# DorMouse-V1_0.net
KiCad netlist of a schematic drawn in EAGLE
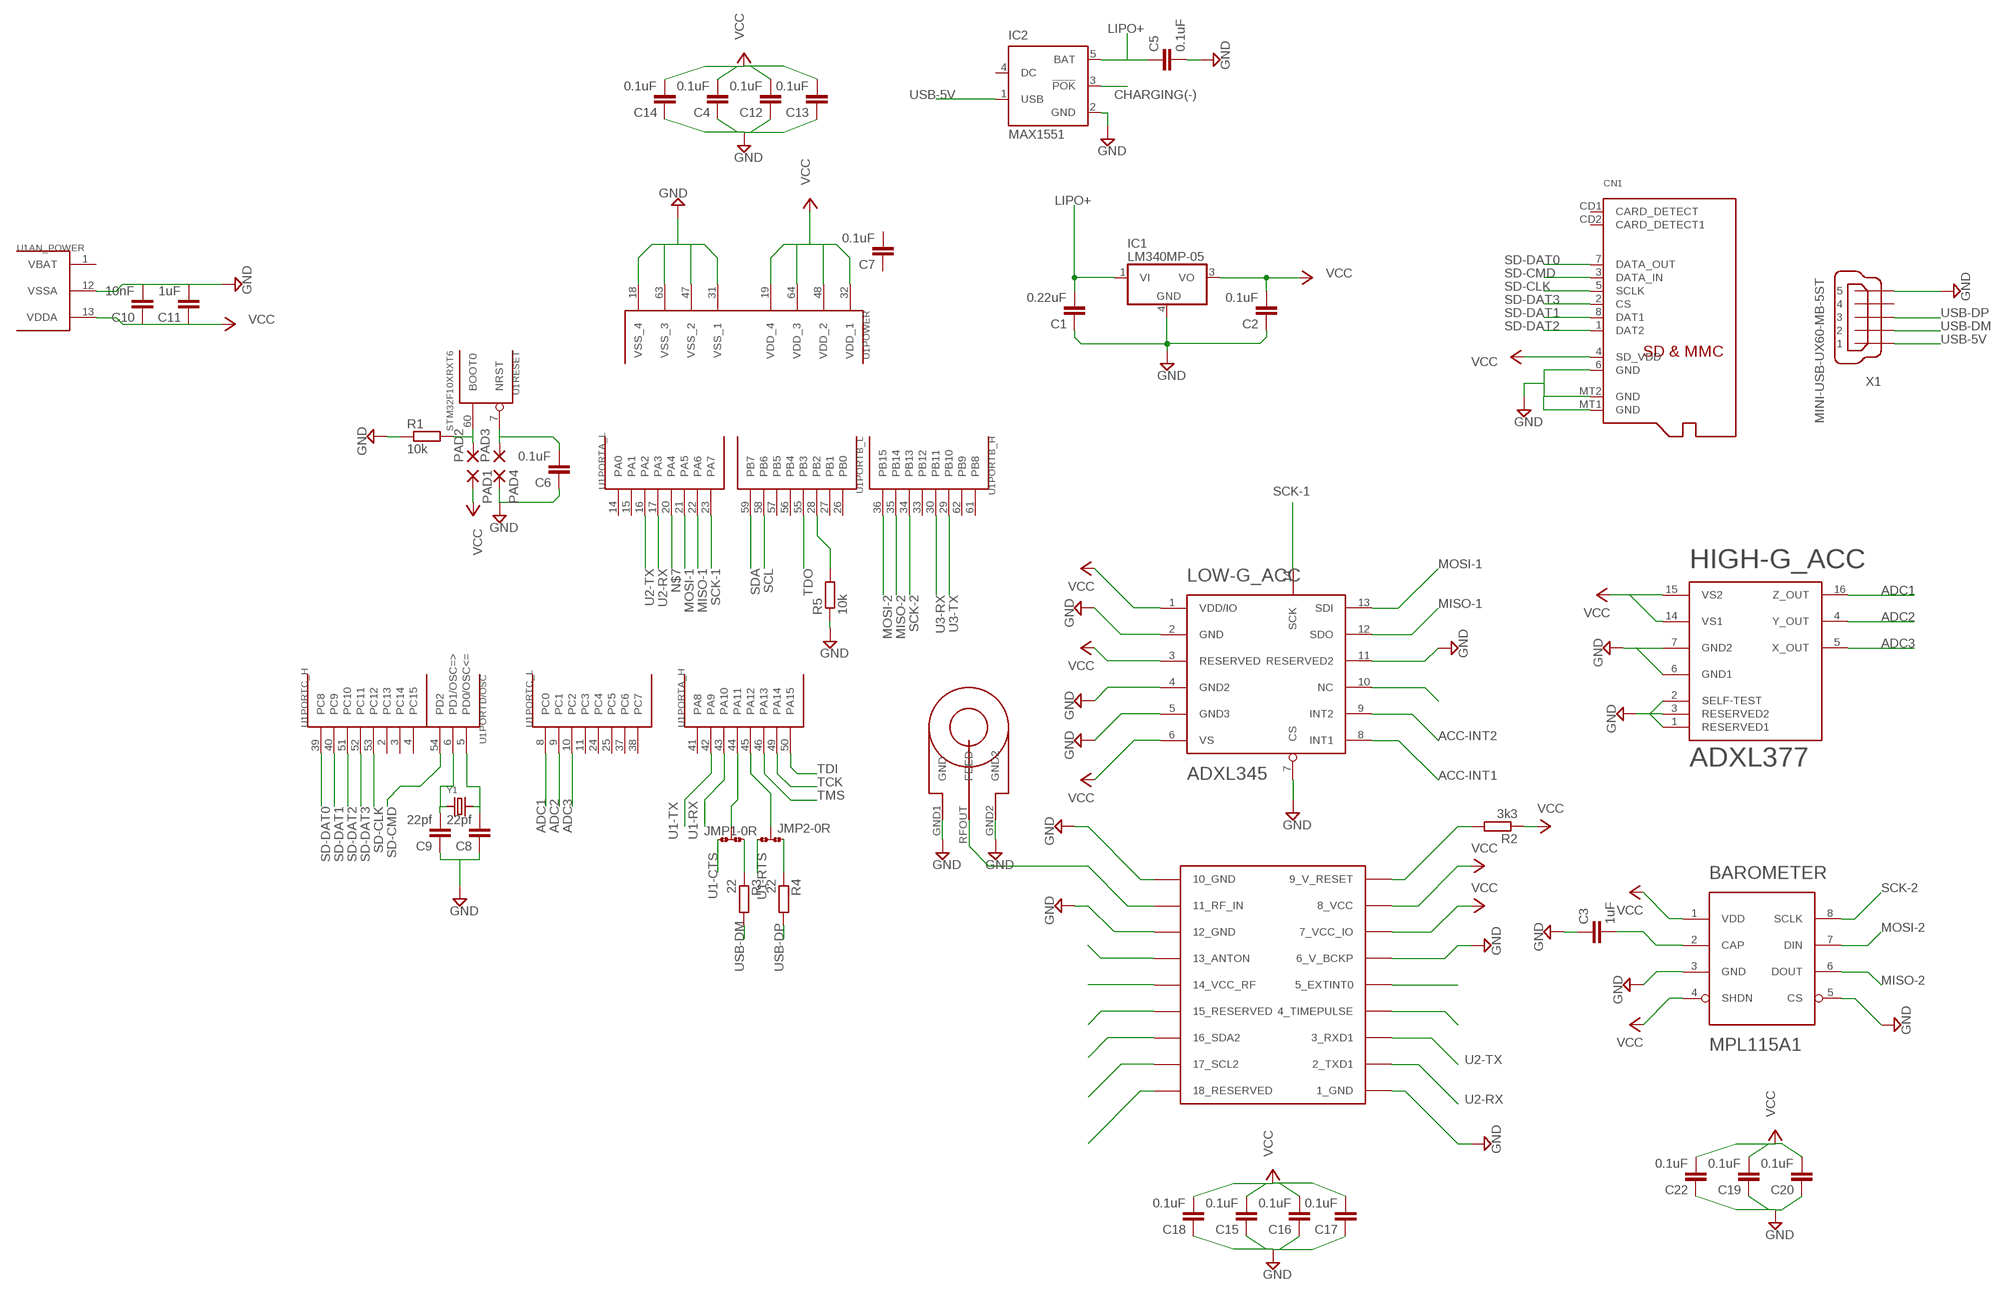
[diagram p0: schematic, sheet 1, part 1 of 2]
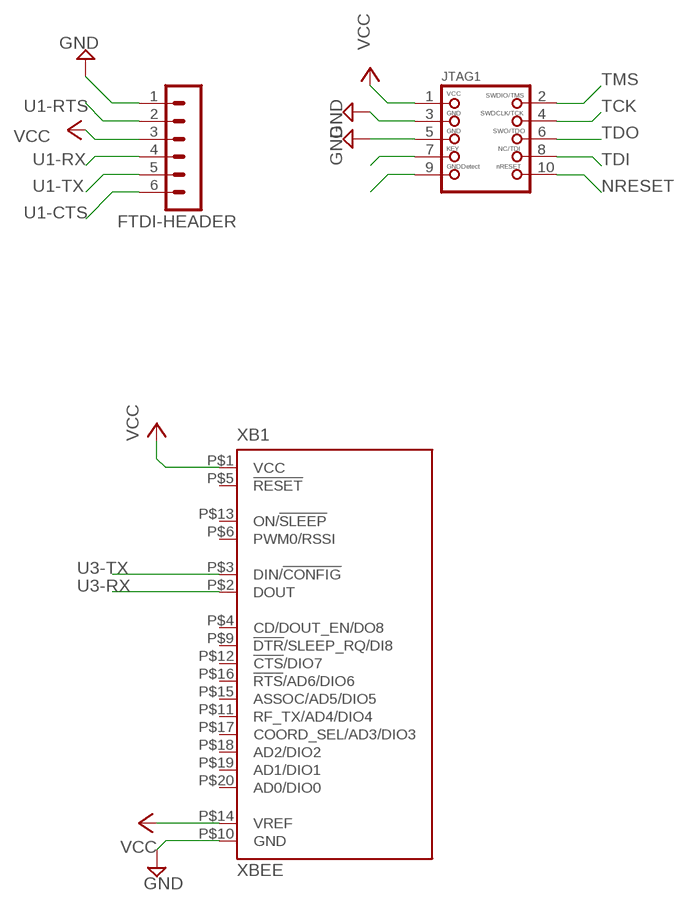
[diagram p1: schematic, sheet 1, part 2 of 2]

(export (version "E")
  (design (tool "Eeschema 10.0.6"))
  (components
    (comp (ref "BAROMETER")
      (value "MPL115A1")
      (footprint "eagle-import:LGA-8")
      (libsource (lib "eagle-import") (part "MPL115A1"))
    )
    (comp (ref "C1")
      (value "0.22uF")
      (footprint "eagle-import:C0402")
      (libsource (lib "eagle-import") (part "C-EUC0402"))
    )
    (comp (ref "C2")
      (value "0.1uF")
      (footprint "eagle-import:C0402")
      (libsource (lib "eagle-import") (part "C-EUC0402"))
    )
    (comp (ref "C3")
      (value "1uF")
      (footprint "eagle-import:C0402")
      (libsource (lib "eagle-import") (part "C-EUC0402"))
    )
    (comp (ref "C4")
      (value "0.1uF")
      (footprint "eagle-import:C0402")
      (libsource (lib "eagle-import") (part "C-EUC0402"))
    )
    (comp (ref "C5")
      (value "0.1uF")
      (footprint "eagle-import:C0402")
      (libsource (lib "eagle-import") (part "C-EUC0402"))
    )
    (comp (ref "C6")
      (value "0.1uF")
      (footprint "eagle-import:C0402")
      (libsource (lib "eagle-import") (part "C-EUC0402"))
    )
    (comp (ref "C7")
      (value "0.1uF")
      (footprint "eagle-import:C0402")
      (libsource (lib "eagle-import") (part "C-EUC0402"))
    )
    (comp (ref "C8")
      (value "22pf")
      (footprint "eagle-import:C0402")
      (libsource (lib "eagle-import") (part "C-EUC0402"))
    )
    (comp (ref "C9")
      (value "22pf")
      (footprint "eagle-import:C0402")
      (libsource (lib "eagle-import") (part "C-EUC0402"))
    )
    (comp (ref "C10")
      (value "10nF")
      (footprint "eagle-import:C0402")
      (libsource (lib "eagle-import") (part "C-EUC0402"))
    )
    (comp (ref "C11")
      (value "1uF")
      (footprint "eagle-import:C0402")
      (libsource (lib "eagle-import") (part "C-EUC0402"))
    )
    (comp (ref "C12")
      (value "0.1uF")
      (footprint "eagle-import:C0402")
      (libsource (lib "eagle-import") (part "C-EUC0402"))
    )
    (comp (ref "C13")
      (value "0.1uF")
      (footprint "eagle-import:C0402")
      (libsource (lib "eagle-import") (part "C-EUC0402"))
    )
    (comp (ref "C14")
      (value "0.1uF")
      (footprint "eagle-import:C0402")
      (libsource (lib "eagle-import") (part "C-EUC0402"))
    )
    (comp (ref "C15")
      (value "0.1uF")
      (footprint "eagle-import:C0402")
      (libsource (lib "eagle-import") (part "C-EUC0402"))
    )
    (comp (ref "C16")
      (value "0.1uF")
      (footprint "eagle-import:C0402")
      (libsource (lib "eagle-import") (part "C-EUC0402"))
    )
    (comp (ref "C17")
      (value "0.1uF")
      (footprint "eagle-import:C0402")
      (libsource (lib "eagle-import") (part "C-EUC0402"))
    )
    (comp (ref "C18")
      (value "0.1uF")
      (footprint "eagle-import:C0402")
      (libsource (lib "eagle-import") (part "C-EUC0402"))
    )
    (comp (ref "C19")
      (value "0.1uF")
      (footprint "eagle-import:C0402")
      (libsource (lib "eagle-import") (part "C-EUC0402"))
    )
    (comp (ref "C20")
      (value "0.1uF")
      (footprint "eagle-import:C0402")
      (libsource (lib "eagle-import") (part "C-EUC0402"))
    )
    (comp (ref "C22")
      (value "0.1uF")
      (footprint "eagle-import:C0402")
      (libsource (lib "eagle-import") (part "C-EUC0402"))
    )
    (comp (ref "CN1")
      (value "MICROSD")
      (footprint "eagle-import:MICROSD")
      (libsource (lib "eagle-import") (part "MICROSD"))
    )
    (comp (ref "FTDI-HEADER")
      (value "MA06-1")
      (footprint "eagle-import:MA06-1")
      (libsource (lib "eagle-import") (part "MA06-1"))
    )
    (comp (ref "GPS")
      (value "UBLOX_MAX-6")
      (footprint "eagle-import:UBLOX_MAX-6")
      (libsource (lib "eagle-import") (part "UBLOX_MAX-6"))
    )
    (comp (ref "HIGH-G_ACC")
      (value "ADXL377")
      (footprint "eagle-import:LFCSP-16")
      (libsource (lib "eagle-import") (part "ADXL377"))
    )
    (comp (ref "IC1")
      (value "LM340MP-05")
      (footprint "eagle-import:SOT223")
      (libsource (lib "eagle-import") (part "LM340?-MP05"))
    )
    (comp (ref "IC2")
      (value "MAX1551")
      (footprint "eagle-import:SOT23-5L")
      (fields (field (name "MF") "MAXIM") (field (name "MPN") "MAX1551EZK-T"))
      (libsource (lib "eagle-import") (part "MAX1551"))
    )
    (comp (ref "JMP1")
      (value "0R-JUMPA")
      (footprint "eagle-import:A0R-JMP")
      (libsource (lib "eagle-import") (part "0R-JUMPA"))
    )
    (comp (ref "JMP2")
      (value "0R-JUMPA")
      (footprint "eagle-import:A0R-JMP")
      (libsource (lib "eagle-import") (part "0R-JUMPA"))
    )
    (comp (ref "JTAG1")
      (value "JTAG-CORTEXM3")
      (footprint "eagle-import:2X05_1.27MM_SMT")
      (libsource (lib "eagle-import") (part "JTAG-CORTEXM3"))
    )
    (comp (ref "LOW-G_ACC")
      (value "ADXL345")
      (footprint "eagle-import:LGA-14")
      (libsource (lib "eagle-import") (part "ADXL345"))
    )
    (comp (ref "PAD1")
      (value "SMD2")
      (footprint "eagle-import:SMD1,27-2,54")
      (libsource (lib "eagle-import") (part "SMD2"))
    )
    (comp (ref "PAD2")
      (value "SMD2")
      (footprint "eagle-import:SMD1,27-2,54")
      (libsource (lib "eagle-import") (part "SMD2"))
    )
    (comp (ref "PAD3")
      (value "SMD2")
      (footprint "eagle-import:SMD1,27-2,54")
      (libsource (lib "eagle-import") (part "SMD2"))
    )
    (comp (ref "PAD4")
      (value "SMD2")
      (footprint "eagle-import:SMD1,27-2,54")
      (libsource (lib "eagle-import") (part "SMD2"))
    )
    (comp (ref "R1")
      (value "10k")
      (footprint "eagle-import:R0402")
      (libsource (lib "eagle-import") (part "R-EU_R0402"))
    )
    (comp (ref "R2")
      (value "3k3")
      (footprint "eagle-import:R0402")
      (libsource (lib "eagle-import") (part "R-EU_R0402"))
    )
    (comp (ref "R3")
      (value "22")
      (footprint "eagle-import:R0402")
      (libsource (lib "eagle-import") (part "R-EU_R0402"))
    )
    (comp (ref "R4")
      (value "22")
      (footprint "eagle-import:R0402")
      (libsource (lib "eagle-import") (part "R-EU_R0402"))
    )
    (comp (ref "R5")
      (value "10k")
      (footprint "eagle-import:R0402")
      (libsource (lib "eagle-import") (part "R-EU_R0402"))
    )
    (comp (ref "U$1")
      (value "SARANTEL-SL1204")
      (footprint "eagle-import:SARANTEL-SL1204")
      (libsource (lib "eagle-import") (part "SARANTEL-SL1204"))
    )
    (comp (ref "U1")
      (value "STM32F10XRXT6")
      (footprint "eagle-import:TQFP64")
      (libsource (lib "eagle-import") (part "STM32F10XRXT6"))
    )
    (comp (ref "X1")
      (value "MINI-USB-UX60-MB-5ST")
      (footprint "eagle-import:UX60-MB-5ST")
      (libsource (lib "eagle-import") (part "MINI-USB-UX60-MB-5ST"))
    )
    (comp (ref "XB1")
      (value "XBEE")
      (footprint "eagle-import:XBEE")
      (fields (field (name "MPN") "XBP24-Z7UIT-004"))
      (libsource (lib "eagle-import") (part "XBEE"))
    )
    (comp (ref "Y1")
      (value "CRYSTALSMD")
      (footprint "eagle-import:HC49UP")
      (libsource (lib "eagle-import") (part "CRYSTALSMD"))
    )
  )
  (nets
    (net (code "1") (name "/ACC-INT1") (class "Default")
      (node (ref "LOW-G_ACC") (pin "8") (pinfunction "INT1_8") (pintype "bidirectional"))
    )
    (net (code "2") (name "/ACC-INT2") (class "Default")
      (node (ref "LOW-G_ACC") (pin "9") (pinfunction "INT2_9") (pintype "bidirectional"))
    )
    (net (code "3") (name "/ADC1") (class "Default")
      (node (ref "HIGH-G_ACC") (pin "16") (pinfunction "Z_OUT_16") (pintype "bidirectional"))
      (node (ref "U1") (pin "8") (pinfunction "PC0_8") (pintype "bidirectional"))
    )
    (net (code "4") (name "/ADC2") (class "Default")
      (node (ref "HIGH-G_ACC") (pin "4") (pinfunction "Y_OUT_4") (pintype "bidirectional"))
      (node (ref "U1") (pin "9") (pinfunction "PC1_9") (pintype "bidirectional"))
    )
    (net (code "5") (name "/ADC3") (class "Default")
      (node (ref "HIGH-G_ACC") (pin "5") (pinfunction "X_OUT_5") (pintype "bidirectional"))
      (node (ref "U1") (pin "10") (pinfunction "PC2_10") (pintype "bidirectional"))
    )
    (net (code "6") (name "/CHARGING(-)") (class "Default")
      (node (ref "IC2") (pin "3") (pinfunction "~{POK}_3") (pintype "output"))
    )
    (net (code "7") (name "/LIPO+") (class "Default")
      (node (ref "C1") (pin "2") (pinfunction "2_2") (pintype "passive"))
      (node (ref "C5") (pin "1") (pinfunction "1_1") (pintype "passive"))
      (node (ref "IC1") (pin "1") (pinfunction "VI_1") (pintype "input"))
      (node (ref "IC2") (pin "5") (pinfunction "BAT_5") (pintype "passive"))
    )
    (net (code "8") (name "/MISO-1") (class "Default")
      (node (ref "LOW-G_ACC") (pin "12") (pinfunction "SDO_12") (pintype "bidirectional"))
      (node (ref "U1") (pin "22") (pinfunction "PA6_22") (pintype "bidirectional"))
    )
    (net (code "9") (name "/MISO-2") (class "Default")
      (node (ref "BAROMETER") (pin "6") (pinfunction "DOUT_6") (pintype "bidirectional"))
      (node (ref "U1") (pin "35") (pinfunction "PB14_35") (pintype "bidirectional"))
    )
    (net (code "10") (name "/MOSI-1") (class "Default")
      (node (ref "LOW-G_ACC") (pin "13") (pinfunction "SDI_13") (pintype "bidirectional"))
      (node (ref "U1") (pin "21") (pinfunction "PA5_21") (pintype "bidirectional"))
    )
    (net (code "11") (name "/MOSI-2") (class "Default")
      (node (ref "BAROMETER") (pin "7") (pinfunction "DIN_7") (pintype "bidirectional"))
      (node (ref "U1") (pin "36") (pinfunction "PB15_36") (pintype "bidirectional"))
    )
    (net (code "12") (name "/N$7") (class "Default")
      (node (ref "U1") (pin "20") (pinfunction "PA4_20") (pintype "bidirectional"))
    )
    (net (code "13") (name "/NRESET") (class "Default")
      (node (ref "JTAG1") (pin "10") (pinfunction "10_10") (pintype "passive"))
    )
    (net (code "14") (name "/SCK-1") (class "Default")
      (node (ref "LOW-G_ACC") (pin "14") (pinfunction "SCK_14") (pintype "bidirectional"))
      (node (ref "U1") (pin "23") (pinfunction "PA7_23") (pintype "bidirectional"))
    )
    (net (code "15") (name "/SCK-2") (class "Default")
      (node (ref "BAROMETER") (pin "8") (pinfunction "SCLK_8") (pintype "bidirectional"))
      (node (ref "U1") (pin "34") (pinfunction "PB13_34") (pintype "bidirectional"))
    )
    (net (code "16") (name "/SCL") (class "Default")
      (node (ref "U1") (pin "58") (pinfunction "PB6_58") (pintype "bidirectional"))
    )
    (net (code "17") (name "/SD-CLK") (class "Default")
      (node (ref "CN1") (pin "5") (pinfunction "SCLK_5") (pintype "input"))
      (node (ref "U1") (pin "53") (pinfunction "PC12_53") (pintype "bidirectional"))
    )
    (net (code "18") (name "/SD-CMD") (class "Default")
      (node (ref "CN1") (pin "3") (pinfunction "DATA_IN_3") (pintype "input"))
      (node (ref "U1") (pin "54") (pinfunction "PD2_54") (pintype "bidirectional"))
    )
    (net (code "19") (name "/SD-DAT0") (class "Default")
      (node (ref "CN1") (pin "7") (pinfunction "DATA_OUT_7") (pintype "output"))
      (node (ref "U1") (pin "39") (pinfunction "PC8_39") (pintype "bidirectional"))
    )
    (net (code "20") (name "/SD-DAT1") (class "Default")
      (node (ref "CN1") (pin "8") (pinfunction "DAT1_8") (pintype "bidirectional"))
      (node (ref "U1") (pin "40") (pinfunction "PC9_40") (pintype "bidirectional"))
    )
    (net (code "21") (name "/SD-DAT2") (class "Default")
      (node (ref "CN1") (pin "1") (pinfunction "DAT2_1") (pintype "bidirectional"))
      (node (ref "U1") (pin "51") (pinfunction "PC10_51") (pintype "bidirectional"))
    )
    (net (code "22") (name "/SD-DAT3") (class "Default")
      (node (ref "CN1") (pin "2") (pinfunction "CS_2") (pintype "input"))
      (node (ref "U1") (pin "52") (pinfunction "PC11_52") (pintype "bidirectional"))
    )
    (net (code "23") (name "/SDA") (class "Default")
      (node (ref "U1") (pin "59") (pinfunction "PB7_59") (pintype "bidirectional"))
    )
    (net (code "24") (name "/TCK") (class "Default")
      (node (ref "JTAG1") (pin "4") (pinfunction "4_4") (pintype "passive"))
      (node (ref "U1") (pin "49") (pinfunction "PA14_49") (pintype "bidirectional"))
    )
    (net (code "25") (name "/TDI") (class "Default")
      (node (ref "JTAG1") (pin "8") (pinfunction "8_8") (pintype "passive"))
      (node (ref "U1") (pin "50") (pinfunction "PA15_50") (pintype "bidirectional"))
    )
    (net (code "26") (name "/TDO") (class "Default")
      (node (ref "JTAG1") (pin "6") (pinfunction "6_6") (pintype "passive"))
      (node (ref "U1") (pin "55") (pinfunction "PB3_55") (pintype "bidirectional"))
    )
    (net (code "27") (name "/TMS") (class "Default")
      (node (ref "JTAG1") (pin "2") (pinfunction "2_2") (pintype "passive"))
      (node (ref "U1") (pin "46") (pinfunction "PA13_46") (pintype "bidirectional"))
    )
    (net (code "28") (name "/U1-CTS") (class "Default")
      (node (ref "FTDI-HEADER") (pin "6") (pinfunction "6_6") (pintype "passive"))
      (node (ref "JMP1") (pin "1") (pinfunction "1_1") (pintype "passive"))
    )
    (net (code "29") (name "/U1-RTS") (class "Default")
      (node (ref "FTDI-HEADER") (pin "2") (pinfunction "2_2") (pintype "passive"))
      (node (ref "JMP2") (pin "1") (pinfunction "1_1") (pintype "passive"))
    )
    (net (code "30") (name "/U1-RX") (class "Default")
      (node (ref "FTDI-HEADER") (pin "4") (pinfunction "4_4") (pintype "passive"))
      (node (ref "U1") (pin "43") (pinfunction "PA10_43") (pintype "bidirectional"))
    )
    (net (code "31") (name "/U1-TX") (class "Default")
      (node (ref "FTDI-HEADER") (pin "5") (pinfunction "5_5") (pintype "passive"))
      (node (ref "U1") (pin "42") (pinfunction "PA9_42") (pintype "bidirectional"))
    )
    (net (code "32") (name "/U2-RX") (class "Default")
      (node (ref "GPS") (pin "2_TXD1") (pinfunction "2_TXD1_2_TXD1") (pintype "bidirectional"))
      (node (ref "U1") (pin "17") (pinfunction "PA3_17") (pintype "bidirectional"))
    )
    (net (code "33") (name "/U2-TX") (class "Default")
      (node (ref "GPS") (pin "3_RXD1") (pinfunction "3_RXD1_3_RXD1") (pintype "bidirectional"))
      (node (ref "U1") (pin "16") (pinfunction "PA2_16") (pintype "bidirectional"))
    )
    (net (code "34") (name "/U3-RX") (class "Default")
      (node (ref "U1") (pin "30") (pinfunction "PB11_30") (pintype "bidirectional"))
      (node (ref "XB1") (pin "P$2") (pinfunction "DOUT_P$2") (pintype "output"))
    )
    (net (code "35") (name "/U3-TX") (class "Default")
      (node (ref "U1") (pin "29") (pinfunction "PB10_29") (pintype "bidirectional"))
      (node (ref "XB1") (pin "P$3") (pinfunction "DIN/~{CONFIG}_P$3") (pintype "input"))
    )
    (net (code "36") (name "/USB-5V") (class "Default")
      (node (ref "IC2") (pin "1") (pinfunction "USB_1") (pintype "input"))
      (node (ref "X1") (pin "1") (pinfunction "1_1") (pintype "input"))
    )
    (net (code "37") (name "/USB-DM") (class "Default")
      (node (ref "R3") (pin "2") (pinfunction "2_2") (pintype "passive"))
      (node (ref "X1") (pin "2") (pinfunction "2_2") (pintype "input"))
    )
    (net (code "38") (name "/USB-DP") (class "Default")
      (node (ref "R4") (pin "2") (pinfunction "2_2") (pintype "passive"))
      (node (ref "X1") (pin "3") (pinfunction "3_3") (pintype "input"))
    )
    (net (code "39") (name "/VBAT") (class "Default")
      (node (ref "U1") (pin "1") (pinfunction "VBAT_1") (pintype "power_in"))
    )
    (net (code "40") (name "GND") (class "Default")
      (node (ref "BAROMETER") (pin "3") (pinfunction "GND_3") (pintype "bidirectional"))
      (node (ref "BAROMETER") (pin "5") (pinfunction "CS_5") (pintype "bidirectional"))
      (node (ref "C1") (pin "1") (pinfunction "1_1") (pintype "passive"))
      (node (ref "C10") (pin "2") (pinfunction "2_2") (pintype "passive"))
      (node (ref "C11") (pin "2") (pinfunction "2_2") (pintype "passive"))
      (node (ref "C12") (pin "1") (pinfunction "1_1") (pintype "passive"))
      (node (ref "C13") (pin "1") (pinfunction "1_1") (pintype "passive"))
      (node (ref "C14") (pin "1") (pinfunction "1_1") (pintype "passive"))
      (node (ref "C15") (pin "1") (pinfunction "1_1") (pintype "passive"))
      (node (ref "C16") (pin "1") (pinfunction "1_1") (pintype "passive"))
      (node (ref "C17") (pin "1") (pinfunction "1_1") (pintype "passive"))
      (node (ref "C18") (pin "1") (pinfunction "1_1") (pintype "passive"))
      (node (ref "C19") (pin "1") (pinfunction "1_1") (pintype "passive"))
      (node (ref "C2") (pin "1") (pinfunction "1_1") (pintype "passive"))
      (node (ref "C20") (pin "1") (pinfunction "1_1") (pintype "passive"))
      (node (ref "C22") (pin "1") (pinfunction "1_1") (pintype "passive"))
      (node (ref "C3") (pin "1") (pinfunction "1_1") (pintype "passive"))
      (node (ref "C4") (pin "1") (pinfunction "1_1") (pintype "passive"))
      (node (ref "C5") (pin "2") (pinfunction "2_2") (pintype "passive"))
      (node (ref "C6") (pin "1") (pinfunction "1_1") (pintype "passive"))
      (node (ref "C8") (pin "1") (pinfunction "1_1") (pintype "passive"))
      (node (ref "C9") (pin "1") (pinfunction "1_1") (pintype "passive"))
      (node (ref "CN1") (pin "6") (pinfunction "GND_6") (pintype "power_in"))
      (node (ref "CN1") (pin "MT1") (pinfunction "GND_MT1") (pintype "power_in"))
      (node (ref "CN1") (pin "MT2") (pinfunction "GND_MT2") (pintype "power_in"))
      (node (ref "FTDI-HEADER") (pin "1") (pinfunction "1_1") (pintype "passive"))
      (node (ref "GPS") (pin "10_GND") (pinfunction "10_GND_10_GND") (pintype "power_in"))
      (node (ref "GPS") (pin "12_GND") (pinfunction "12_GND_12_GND") (pintype "power_in"))
      (node (ref "GPS") (pin "1_GND") (pinfunction "1_GND_1_GND") (pintype "power_in"))
      (node (ref "GPS") (pin "6_V_BCKP") (pinfunction "6_V_BCKP_6_V_BCKP") (pintype "bidirectional"))
      (node (ref "HIGH-G_ACC") (pin "1") (pinfunction "RESERVED1_1") (pintype "bidirectional"))
      (node (ref "HIGH-G_ACC") (pin "2") (pinfunction "SELF-TEST_2") (pintype "bidirectional"))
      (node (ref "HIGH-G_ACC") (pin "3") (pinfunction "RESERVED2_3") (pintype "bidirectional"))
      (node (ref "HIGH-G_ACC") (pin "6") (pinfunction "GND1_6") (pintype "bidirectional"))
      (node (ref "HIGH-G_ACC") (pin "7") (pinfunction "GND2_7") (pintype "bidirectional"))
      (node (ref "IC1") (pin "4") (pinfunction "GND_4") (pintype "passive"))
      (node (ref "IC2") (pin "2") (pinfunction "GND_2") (pintype "power_in"))
      (node (ref "JTAG1") (pin "3") (pinfunction "3_3") (pintype "passive"))
      (node (ref "JTAG1") (pin "5") (pinfunction "5_5") (pintype "passive"))
      (node (ref "LOW-G_ACC") (pin "11") (pinfunction "RESERVED2_11") (pintype "bidirectional"))
      (node (ref "LOW-G_ACC") (pin "2") (pinfunction "GND_2") (pintype "bidirectional"))
      (node (ref "LOW-G_ACC") (pin "4") (pinfunction "GND2_4") (pintype "bidirectional"))
      (node (ref "LOW-G_ACC") (pin "5") (pinfunction "GND3_5") (pintype "bidirectional"))
      (node (ref "LOW-G_ACC") (pin "7") (pinfunction "CS_7") (pintype "bidirectional"))
      (node (ref "PAD4") (pin "1") (pinfunction "P_1") (pintype "passive"))
      (node (ref "R1") (pin "1") (pinfunction "1_1") (pintype "passive"))
      (node (ref "R5") (pin "1") (pinfunction "1_1") (pintype "passive"))
      (node (ref "U$1") (pin "GND1") (pinfunction "GND_GND1") (pintype "bidirectional"))
      (node (ref "U$1") (pin "GND2") (pinfunction "GND2_GND2") (pintype "bidirectional"))
      (node (ref "U1") (pin "12") (pinfunction "VSSA_12") (pintype "power_in"))
      (node (ref "U1") (pin "18") (pinfunction "VSS_4_18") (pintype "power_in"))
      (node (ref "U1") (pin "31") (pinfunction "VSS_1_31") (pintype "power_in"))
      (node (ref "U1") (pin "47") (pinfunction "VSS_2_47") (pintype "power_in"))
      (node (ref "U1") (pin "63") (pinfunction "VSS_3_63") (pintype "power_in"))
      (node (ref "X1") (pin "5") (pinfunction "5_5") (pintype "input"))
      (node (ref "XB1") (pin "P$10") (pinfunction "GND_P$10") (pintype "power_in"))
    )
    (net (code "41") (name "Net-(BAROMETER-CAP)") (class "Default")
      (node (ref "BAROMETER") (pin "2") (pinfunction "CAP_2") (pintype "bidirectional"))
      (node (ref "C3") (pin "2") (pinfunction "2_2") (pintype "passive"))
    )
    (net (code "42") (name "Net-(GPS-Pad9_V_RESET)") (class "Default")
      (node (ref "GPS") (pin "9_V_RESET") (pinfunction "9_V_RESET_9_V_RESET") (pintype "power_in"))
      (node (ref "R2") (pin "2") (pinfunction "2_2") (pintype "passive"))
    )
    (net (code "43") (name "Net-(JMP1-Pad3)") (class "Default")
      (node (ref "JMP1") (pin "3") (pinfunction "3_3") (pintype "passive"))
      (node (ref "R3") (pin "1") (pinfunction "1_1") (pintype "passive"))
    )
    (net (code "44") (name "Net-(JMP2-Pad3)") (class "Default")
      (node (ref "JMP2") (pin "3") (pinfunction "3_3") (pintype "passive"))
      (node (ref "R4") (pin "1") (pinfunction "1_1") (pintype "passive"))
    )
    (net (code "45") (name "Net-(PAD2-P)") (class "Default")
      (node (ref "PAD2") (pin "1") (pinfunction "P_1") (pintype "passive"))
      (node (ref "R1") (pin "2") (pinfunction "2_2") (pintype "passive"))
      (node (ref "U1") (pin "60") (pinfunction "BOOT0_60") (pintype "input"))
    )
    (net (code "46") (name "Net-(PAD3-P)") (class "Default")
      (node (ref "C6") (pin "2") (pinfunction "2_2") (pintype "passive"))
      (node (ref "PAD3") (pin "1") (pinfunction "P_1") (pintype "passive"))
      (node (ref "U1") (pin "7") (pinfunction "NRST_7") (pintype "input"))
    )
    (net (code "47") (name "Net-(U$1-FEED)") (class "Default")
      (node (ref "GPS") (pin "11_RF_IN") (pinfunction "11_RF_IN_11_RF_IN") (pintype "bidirectional"))
      (node (ref "U$1") (pin "RFOUT") (pinfunction "FEED_RFOUT") (pintype "bidirectional"))
    )
    (net (code "48") (name "Net-(U1B-PA11)") (class "Default")
      (node (ref "JMP1") (pin "2") (pinfunction "2_2") (pintype "passive"))
      (node (ref "U1") (pin "44") (pinfunction "PA11_44") (pintype "bidirectional"))
    )
    (net (code "49") (name "Net-(U1B-PA12)") (class "Default")
      (node (ref "JMP2") (pin "2") (pinfunction "2_2") (pintype "passive"))
      (node (ref "U1") (pin "45") (pinfunction "PA12_45") (pintype "bidirectional"))
    )
    (net (code "50") (name "Net-(U1E-PB2)") (class "Default")
      (node (ref "R5") (pin "2") (pinfunction "2_2") (pintype "passive"))
      (node (ref "U1") (pin "28") (pinfunction "PB2_28") (pintype "bidirectional"))
    )
    (net (code "51") (name "Net-(U1H-PD0{slash}OSC<=)") (class "Default")
      (node (ref "C8") (pin "2") (pinfunction "2_2") (pintype "passive"))
      (node (ref "U1") (pin "5") (pinfunction "PD0/OSC<=_5") (pintype "bidirectional"))
      (node (ref "Y1") (pin "2") (pinfunction "2_2") (pintype "passive"))
    )
    (net (code "52") (name "Net-(U1H-PD1{slash}OSC=>)") (class "Default")
      (node (ref "C9") (pin "2") (pinfunction "2_2") (pintype "passive"))
      (node (ref "U1") (pin "6") (pinfunction "PD1/OSC=>_6") (pintype "bidirectional"))
      (node (ref "Y1") (pin "1") (pinfunction "1_1") (pintype "passive"))
    )
    (net (code "53") (name "VCC") (class "Default")
      (node (ref "BAROMETER") (pin "1") (pinfunction "VDD_1") (pintype "bidirectional"))
      (node (ref "BAROMETER") (pin "4") (pinfunction "SHDN_4") (pintype "bidirectional"))
      (node (ref "C10") (pin "1") (pinfunction "1_1") (pintype "passive"))
      (node (ref "C11") (pin "1") (pinfunction "1_1") (pintype "passive"))
      (node (ref "C12") (pin "2") (pinfunction "2_2") (pintype "passive"))
      (node (ref "C13") (pin "2") (pinfunction "2_2") (pintype "passive"))
      (node (ref "C14") (pin "2") (pinfunction "2_2") (pintype "passive"))
      (node (ref "C15") (pin "2") (pinfunction "2_2") (pintype "passive"))
      (node (ref "C16") (pin "2") (pinfunction "2_2") (pintype "passive"))
      (node (ref "C17") (pin "2") (pinfunction "2_2") (pintype "passive"))
      (node (ref "C18") (pin "2") (pinfunction "2_2") (pintype "passive"))
      (node (ref "C19") (pin "2") (pinfunction "2_2") (pintype "passive"))
      (node (ref "C2") (pin "2") (pinfunction "2_2") (pintype "passive"))
      (node (ref "C20") (pin "2") (pinfunction "2_2") (pintype "passive"))
      (node (ref "C22") (pin "2") (pinfunction "2_2") (pintype "passive"))
      (node (ref "C4") (pin "2") (pinfunction "2_2") (pintype "passive"))
      (node (ref "CN1") (pin "4") (pinfunction "SD_VDD_4") (pintype "power_in"))
      (node (ref "FTDI-HEADER") (pin "3") (pinfunction "3_3") (pintype "passive"))
      (node (ref "GPS") (pin "7_VCC_IO") (pinfunction "7_VCC_IO_7_VCC_IO") (pintype "power_in"))
      (node (ref "GPS") (pin "8_VCC") (pinfunction "8_VCC_8_VCC") (pintype "power_in"))
      (node (ref "HIGH-G_ACC") (pin "14") (pinfunction "VS1_14") (pintype "bidirectional"))
      (node (ref "HIGH-G_ACC") (pin "15") (pinfunction "VS2_15") (pintype "bidirectional"))
      (node (ref "IC1") (pin "3") (pinfunction "VO_3") (pintype "passive"))
      (node (ref "JTAG1") (pin "1") (pinfunction "1_1") (pintype "passive"))
      (node (ref "LOW-G_ACC") (pin "1") (pinfunction "VDD/IO_1") (pintype "bidirectional"))
      (node (ref "LOW-G_ACC") (pin "3") (pinfunction "RESERVED_3") (pintype "bidirectional"))
      (node (ref "LOW-G_ACC") (pin "6") (pinfunction "VS_6") (pintype "bidirectional"))
      (node (ref "PAD1") (pin "1") (pinfunction "P_1") (pintype "passive"))
      (node (ref "R2") (pin "1") (pinfunction "1_1") (pintype "passive"))
      (node (ref "U1") (pin "13") (pinfunction "VDDA_13") (pintype "power_in"))
      (node (ref "U1") (pin "19") (pinfunction "VDD_4_19") (pintype "power_in"))
      (node (ref "U1") (pin "32") (pinfunction "VDD_1_32") (pintype "power_in"))
      (node (ref "U1") (pin "48") (pinfunction "VDD_2_48") (pintype "power_in"))
      (node (ref "U1") (pin "64") (pinfunction "VDD_3_64") (pintype "power_in"))
      (node (ref "XB1") (pin "P$1") (pinfunction "VCC_P$1") (pintype "power_in"))
      (node (ref "XB1") (pin "P$14") (pinfunction "VREF_P$14") (pintype "input"))
    )
    (net (code "54") (name "unconnected-(C7-Pad1)") (class "Default")
      (node (ref "C7") (pin "1") (pinfunction "1_1") (pintype "passive"))
    )
    (net (code "55") (name "unconnected-(C7-Pad2)") (class "Default")
      (node (ref "C7") (pin "2") (pinfunction "2_2") (pintype "passive"))
    )
    (net (code "56") (name "unconnected-(CN1-CARD_DETECT-PadCD1)") (class "Default")
      (node (ref "CN1") (pin "CD1") (pinfunction "CARD_DETECT_CD1") (pintype "passive"))
    )
    (net (code "57") (name "unconnected-(CN1-CARD_DETECT1-PadCD2)") (class "Default")
      (node (ref "CN1") (pin "CD2") (pinfunction "CARD_DETECT1_CD2") (pintype "passive"))
    )
    (net (code "58") (name "unconnected-(GPS-Pad4_TIMEPULSE)") (class "Default")
      (node (ref "GPS") (pin "4_TIMEPULSE") (pinfunction "4_TIMEPULSE_4_TIMEPULSE") (pintype "bidirectional"))
    )
    (net (code "59") (name "unconnected-(GPS-Pad5_EXTINT0)") (class "Default")
      (node (ref "GPS") (pin "5_EXTINT0") (pinfunction "5_EXTINT0_5_EXTINT0") (pintype "bidirectional"))
    )
    (net (code "60") (name "unconnected-(GPS-Pad13_ANTON)") (class "Default")
      (node (ref "GPS") (pin "13_ANTON") (pinfunction "13_ANTON_13_ANTON") (pintype "bidirectional"))
    )
    (net (code "61") (name "unconnected-(GPS-Pad14_VCC_RF)") (class "Default")
      (node (ref "GPS") (pin "14_VCC_RF") (pinfunction "14_VCC_RF_14_VCC_RF") (pintype "bidirectional"))
    )
    (net (code "62") (name "unconnected-(GPS-Pad15_RESERVED)") (class "Default")
      (node (ref "GPS") (pin "15_RESERVED") (pinfunction "15_RESERVED_15_RESERVED") (pintype "bidirectional"))
    )
    (net (code "63") (name "unconnected-(GPS-Pad16_SDA2)") (class "Default")
      (node (ref "GPS") (pin "16_SDA2") (pinfunction "16_SDA2_16_SDA2") (pintype "bidirectional"))
    )
    (net (code "64") (name "unconnected-(GPS-Pad17_SCL2)") (class "Default")
      (node (ref "GPS") (pin "17_SCL2") (pinfunction "17_SCL2_17_SCL2") (pintype "bidirectional"))
    )
    (net (code "65") (name "unconnected-(GPS-Pad18_RESERVED)") (class "Default")
      (node (ref "GPS") (pin "18_RESERVED") (pinfunction "18_RESERVED_18_RESERVED") (pintype "bidirectional"))
    )
    (net (code "66") (name "unconnected-(IC2-DC-Pad4)") (class "Default")
      (node (ref "IC2") (pin "4") (pinfunction "DC_4") (pintype "input"))
    )
    (net (code "67") (name "unconnected-(JTAG1-Pad7)") (class "Default")
      (node (ref "JTAG1") (pin "7") (pinfunction "7_7") (pintype "passive"))
    )
    (net (code "68") (name "unconnected-(JTAG1-Pad9)") (class "Default")
      (node (ref "JTAG1") (pin "9") (pinfunction "9_9") (pintype "passive"))
    )
    (net (code "69") (name "unconnected-(LOW-G_ACC-NC-Pad10)") (class "Default")
      (node (ref "LOW-G_ACC") (pin "10") (pinfunction "NC_10") (pintype "bidirectional"))
    )
    (net (code "70") (name "unconnected-(U1B-PA8-Pad41)") (class "Default")
      (node (ref "U1") (pin "41") (pinfunction "PA8_41") (pintype "bidirectional"))
    )
    (net (code "71") (name "unconnected-(U1C-PA0-Pad14)") (class "Default")
      (node (ref "U1") (pin "14") (pinfunction "PA0_14") (pintype "bidirectional"))
    )
    (net (code "72") (name "unconnected-(U1C-PA1-Pad15)") (class "Default")
      (node (ref "U1") (pin "15") (pinfunction "PA1_15") (pintype "bidirectional"))
    )
    (net (code "73") (name "unconnected-(U1D-PB8-Pad61)") (class "Default")
      (node (ref "U1") (pin "61") (pinfunction "PB8_61") (pintype "bidirectional"))
    )
    (net (code "74") (name "unconnected-(U1D-PB9-Pad62)") (class "Default")
      (node (ref "U1") (pin "62") (pinfunction "PB9_62") (pintype "bidirectional"))
    )
    (net (code "75") (name "unconnected-(U1D-PB12-Pad33)") (class "Default")
      (node (ref "U1") (pin "33") (pinfunction "PB12_33") (pintype "bidirectional"))
    )
    (net (code "76") (name "unconnected-(U1E-PB0-Pad26)") (class "Default")
      (node (ref "U1") (pin "26") (pinfunction "PB0_26") (pintype "bidirectional"))
    )
    (net (code "77") (name "unconnected-(U1E-PB1-Pad27)") (class "Default")
      (node (ref "U1") (pin "27") (pinfunction "PB1_27") (pintype "bidirectional"))
    )
    (net (code "78") (name "unconnected-(U1E-PB4-Pad56)") (class "Default")
      (node (ref "U1") (pin "56") (pinfunction "PB4_56") (pintype "bidirectional"))
    )
    (net (code "79") (name "unconnected-(U1E-PB5-Pad57)") (class "Default")
      (node (ref "U1") (pin "57") (pinfunction "PB5_57") (pintype "bidirectional"))
    )
    (net (code "80") (name "unconnected-(U1F-PC13-Pad2)") (class "Default")
      (node (ref "U1") (pin "2") (pinfunction "PC13_2") (pintype "bidirectional"))
    )
    (net (code "81") (name "unconnected-(U1F-PC14-Pad3)") (class "Default")
      (node (ref "U1") (pin "3") (pinfunction "PC14_3") (pintype "bidirectional"))
    )
    (net (code "82") (name "unconnected-(U1F-PC15-Pad4)") (class "Default")
      (node (ref "U1") (pin "4") (pinfunction "PC15_4") (pintype "bidirectional"))
    )
    (net (code "83") (name "unconnected-(U1G-PC3-Pad11)") (class "Default")
      (node (ref "U1") (pin "11") (pinfunction "PC3_11") (pintype "bidirectional"))
    )
    (net (code "84") (name "unconnected-(U1G-PC4-Pad24)") (class "Default")
      (node (ref "U1") (pin "24") (pinfunction "PC4_24") (pintype "bidirectional"))
    )
    (net (code "85") (name "unconnected-(U1G-PC5-Pad25)") (class "Default")
      (node (ref "U1") (pin "25") (pinfunction "PC5_25") (pintype "bidirectional"))
    )
    (net (code "86") (name "unconnected-(U1G-PC6-Pad37)") (class "Default")
      (node (ref "U1") (pin "37") (pinfunction "PC6_37") (pintype "bidirectional"))
    )
    (net (code "87") (name "unconnected-(U1G-PC7-Pad38)") (class "Default")
      (node (ref "U1") (pin "38") (pinfunction "PC7_38") (pintype "bidirectional"))
    )
    (net (code "88") (name "unconnected-(X1-Pad4)") (class "Default")
      (node (ref "X1") (pin "4") (pinfunction "4_4") (pintype "input"))
    )
    (net (code "89") (name "unconnected-(XB1-AD0{slash}DIO0-PadP$20)") (class "Default")
      (node (ref "XB1") (pin "P$20") (pinfunction "AD0/DIO0_P$20") (pintype "bidirectional"))
    )
    (net (code "90") (name "unconnected-(XB1-AD1{slash}DIO1-PadP$19)") (class "Default")
      (node (ref "XB1") (pin "P$19") (pinfunction "AD1/DIO1_P$19") (pintype "bidirectional"))
    )
    (net (code "91") (name "unconnected-(XB1-AD2{slash}DIO2-PadP$18)") (class "Default")
      (node (ref "XB1") (pin "P$18") (pinfunction "AD2/DIO2_P$18") (pintype "bidirectional"))
    )
    (net (code "92") (name "unconnected-(XB1-ASSOC{slash}AD5{slash}DIO5-PadP$15)") (class "Default")
      (node (ref "XB1") (pin "P$15") (pinfunction "ASSOC/AD5/DIO5_P$15") (pintype "bidirectional"))
    )
    (net (code "93") (name "unconnected-(XB1-CD{slash}DOUT_EN{slash}DO8-PadP$4)") (class "Default")
      (node (ref "XB1") (pin "P$4") (pinfunction "CD/DOUT_EN/DO8_P$4") (pintype "output"))
    )
    (net (code "94") (name "unconnected-(XB1-COORD_SEL{slash}AD3{slash}DIO3-PadP$17)") (class "Default")
      (node (ref "XB1") (pin "P$17") (pinfunction "COORD_SEL/AD3/DIO3_P$17") (pintype "bidirectional"))
    )
    (net (code "95") (name "unconnected-(XB1-ON{slash}~{SLEEP}-PadP$13)") (class "Default")
      (node (ref "XB1") (pin "P$13") (pinfunction "ON/~{SLEEP}_P$13") (pintype "output"))
    )
    (net (code "96") (name "unconnected-(XB1-PWM0{slash}RSSI-PadP$6)") (class "Default")
      (node (ref "XB1") (pin "P$6") (pinfunction "PWM0/RSSI_P$6") (pintype "output"))
    )
    (net (code "97") (name "unconnected-(XB1-RF_TX{slash}AD4{slash}DIO4-PadP$11)") (class "Default")
      (node (ref "XB1") (pin "P$11") (pinfunction "RF_TX/AD4/DIO4_P$11") (pintype "bidirectional"))
    )
    (net (code "98") (name "unconnected-(XB1-~{CTS}{slash}DIO7-PadP$12)") (class "Default")
      (node (ref "XB1") (pin "P$12") (pinfunction "~{CTS}/DIO7_P$12") (pintype "bidirectional"))
    )
    (net (code "99") (name "unconnected-(XB1-~{DTR}{slash}SLEEP_RQ{slash}DI8-PadP$9)") (class "Default")
      (node (ref "XB1") (pin "P$9") (pinfunction "~{DTR}/SLEEP_RQ/DI8_P$9") (pintype "bidirectional"))
    )
    (net (code "100") (name "unconnected-(XB1-~{RESET}-PadP$5)") (class "Default")
      (node (ref "XB1") (pin "P$5") (pinfunction "~{RESET}_P$5") (pintype "input"))
    )
    (net (code "101") (name "unconnected-(XB1-~{RTS}{slash}AD6{slash}DIO6-PadP$16)") (class "Default")
      (node (ref "XB1") (pin "P$16") (pinfunction "~{RTS}/AD6/DIO6_P$16") (pintype "bidirectional"))
    )
  )
)
